# ZynqDDR.net
KiCad netlist of a schematic drawn in Altium Designer
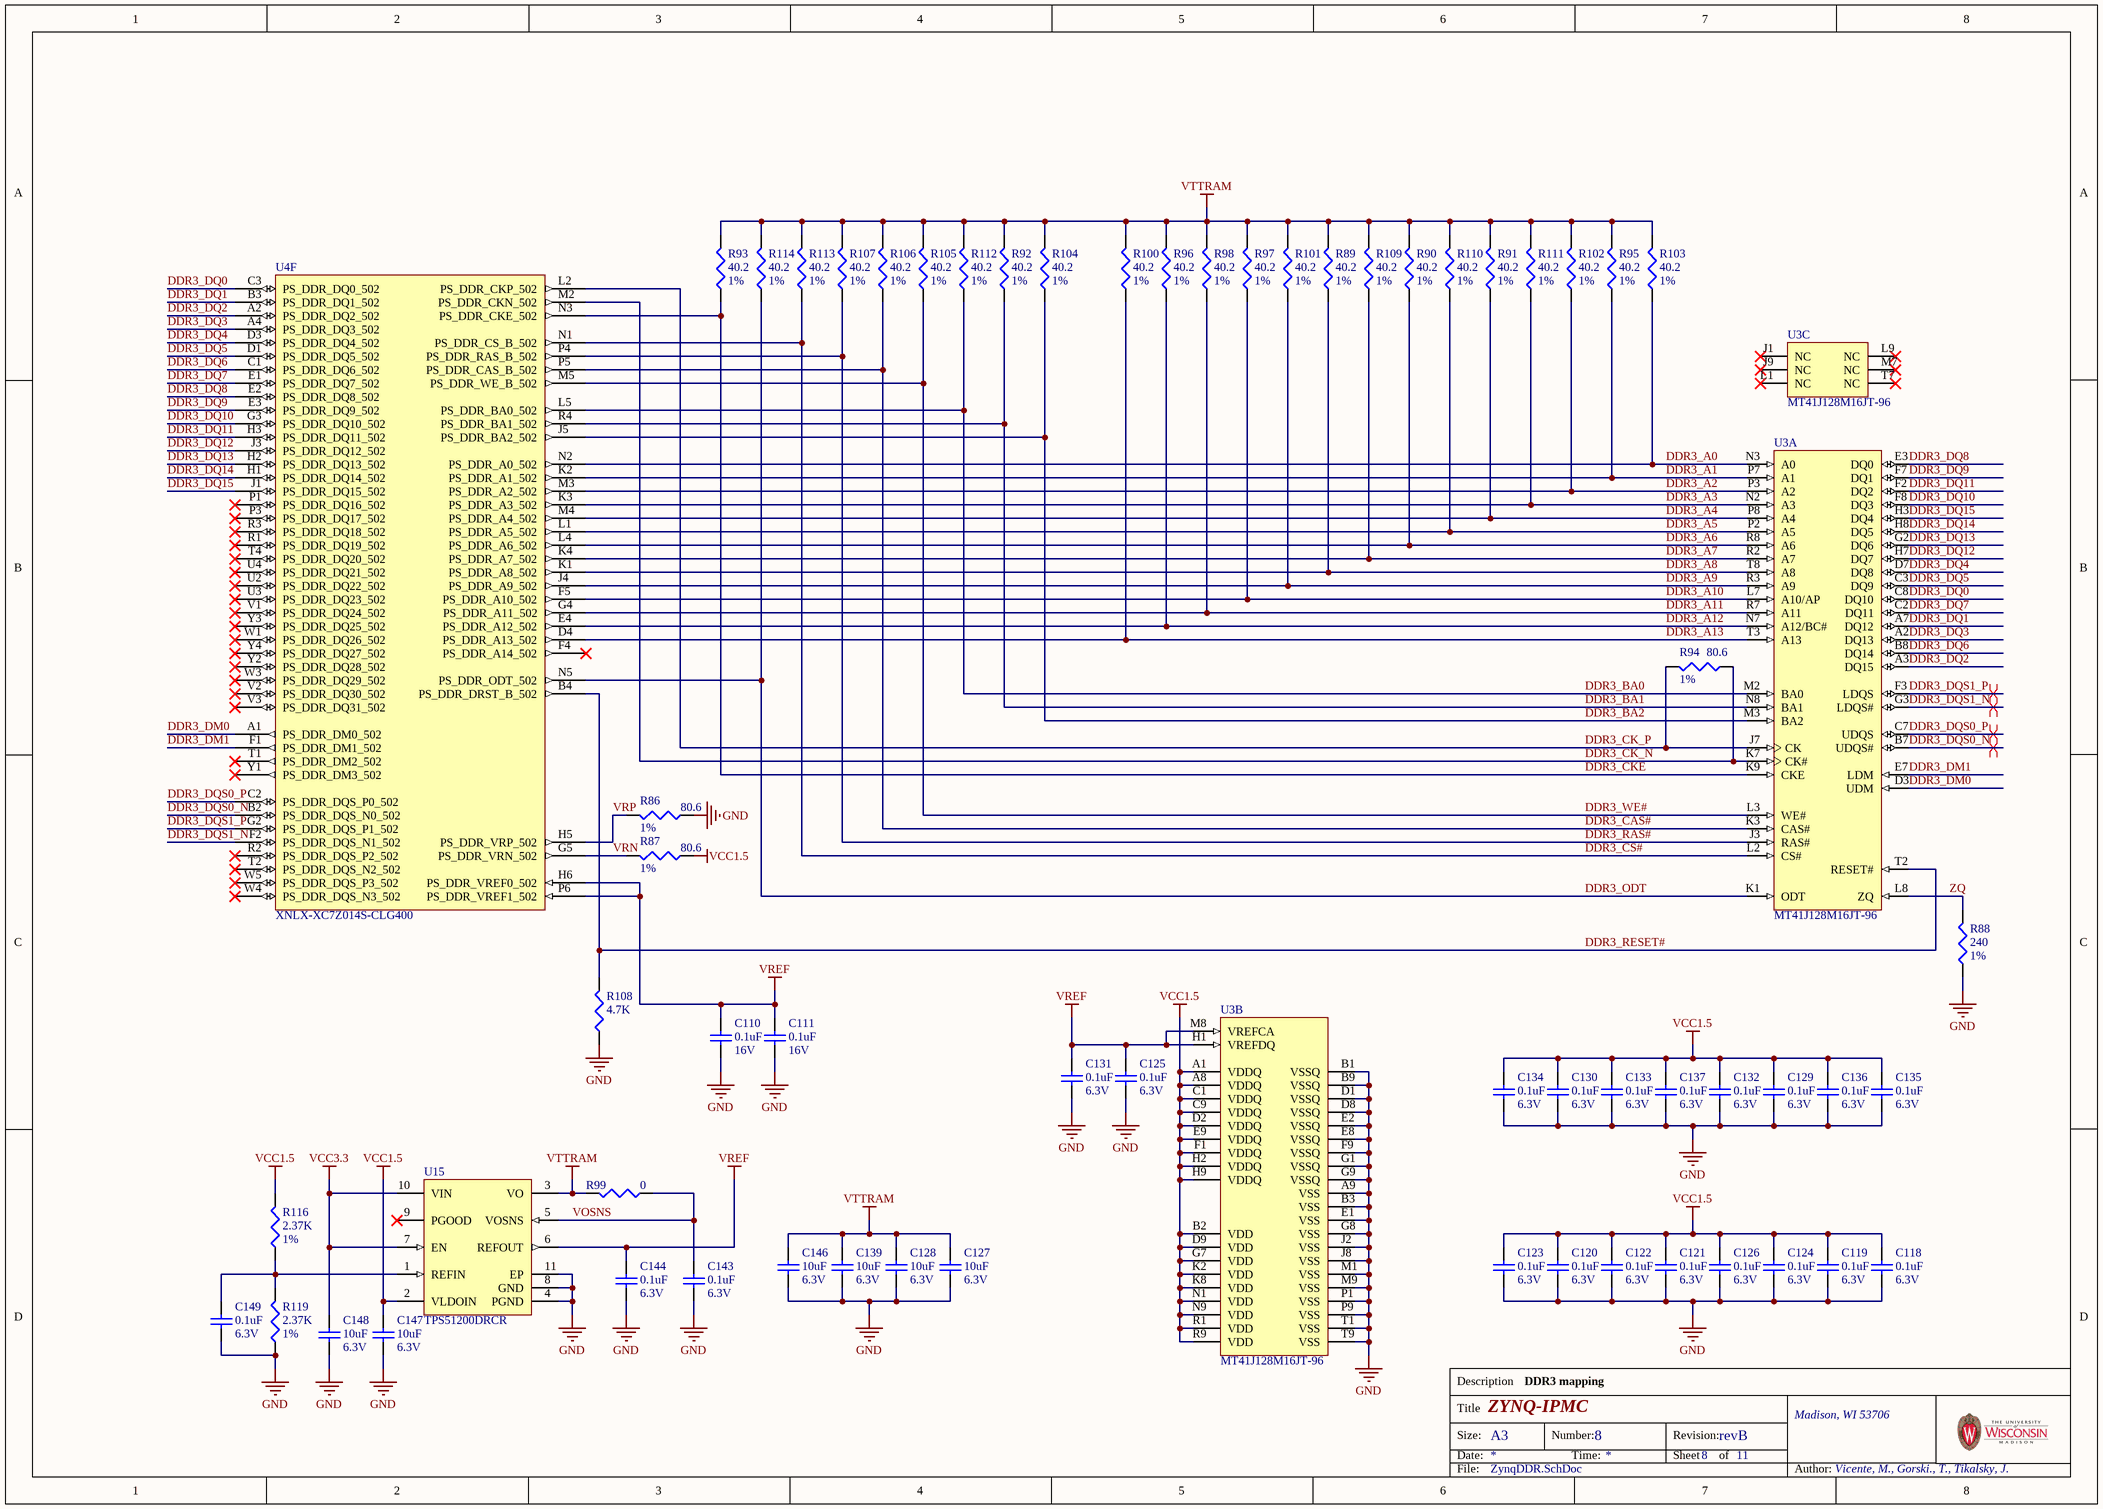
[diagram p0: ZynqDDR.SchDoc]

(export (version "E")
  (design (tool "Eeschema 10.0.6"))
  (components
    (comp (ref "C110")
      (value "0.1uF")
      (footprint "C0402_IPC_H")
      (description "Capacitor")
      (fields
        (field (name "RATING") "16V")
        (field (name "MANUFACTURER") "Murata")
        (field (name "PART") "GRM155R71C104KA88D")
      )
      (libsource (lib "CustomParts") (part "Cap"))
    )
    (comp (ref "C111")
      (value "0.1uF")
      (footprint "C0402_IPC_H")
      (description "Capacitor")
      (fields
        (field (name "RATING") "16V")
        (field (name "MANUFACTURER") "Murata")
        (field (name "PART") "GRM155R71C104KA88D")
      )
      (libsource (lib "CustomParts") (part "Cap"))
    )
    (comp (ref "C118")
      (value "0.1uF")
      (footprint "C0201_IPC_H")
      (description "Capacitor")
      (fields
        (field (name "RATING") "6.3V")
        (field (name "MANUFACTURER") "Murata")
        (field (name "PART") "GRM033R60J104KE19D")
      )
      (libsource (lib "CustomParts") (part "Cap"))
    )
    (comp (ref "C119")
      (value "0.1uF")
      (footprint "C0201_IPC_H")
      (description "Capacitor")
      (fields
        (field (name "RATING") "6.3V")
        (field (name "MANUFACTURER") "Murata")
        (field (name "PART") "GRM033R60J104KE19D")
      )
      (libsource (lib "CustomParts") (part "Cap"))
    )
    (comp (ref "C120")
      (value "0.1uF")
      (footprint "C0201_IPC_H")
      (description "Capacitor")
      (fields
        (field (name "RATING") "6.3V")
        (field (name "MANUFACTURER") "Murata")
        (field (name "PART") "GRM033R60J104KE19D")
      )
      (libsource (lib "CustomParts") (part "Cap"))
    )
    (comp (ref "C121")
      (value "0.1uF")
      (footprint "C0201_IPC_H")
      (description "Capacitor")
      (fields
        (field (name "RATING") "6.3V")
        (field (name "MANUFACTURER") "Murata")
        (field (name "PART") "GRM033R60J104KE19D")
      )
      (libsource (lib "CustomParts") (part "Cap"))
    )
    (comp (ref "C122")
      (value "0.1uF")
      (footprint "C0201_IPC_H")
      (description "Capacitor")
      (fields
        (field (name "RATING") "6.3V")
        (field (name "MANUFACTURER") "Murata")
        (field (name "PART") "GRM033R60J104KE19D")
      )
      (libsource (lib "CustomParts") (part "Cap"))
    )
    (comp (ref "C123")
      (value "0.1uF")
      (footprint "C0201_IPC_H")
      (description "Capacitor")
      (fields
        (field (name "RATING") "6.3V")
        (field (name "MANUFACTURER") "Murata")
        (field (name "PART") "GRM033R60J104KE19D")
      )
      (libsource (lib "CustomParts") (part "Cap"))
    )
    (comp (ref "C124")
      (value "0.1uF")
      (footprint "C0201_IPC_H")
      (description "Capacitor")
      (fields
        (field (name "RATING") "6.3V")
        (field (name "MANUFACTURER") "Murata")
        (field (name "PART") "GRM033R60J104KE19D")
      )
      (libsource (lib "CustomParts") (part "Cap"))
    )
    (comp (ref "C125")
      (value "0.1uF")
      (footprint "C0201_IPC_H")
      (description "Capacitor")
      (fields
        (field (name "RATING") "6.3V")
        (field (name "MANUFACTURER") "Murata")
        (field (name "PART") "GRM033R60J104KE19D")
      )
      (libsource (lib "CustomParts") (part "Cap"))
    )
    (comp (ref "C126")
      (value "0.1uF")
      (footprint "C0201_IPC_H")
      (description "Capacitor")
      (fields
        (field (name "RATING") "6.3V")
        (field (name "MANUFACTURER") "Murata")
        (field (name "PART") "GRM033R60J104KE19D")
      )
      (libsource (lib "CustomParts") (part "Cap"))
    )
    (comp (ref "C127")
      (value "10uF")
      (footprint "C0402_IPC_H")
      (description "Capacitor")
      (fields
        (field (name "RATING") "6.3V")
        (field (name "MANUFACTURER") "Murata")
        (field (name "PART") "GRM155R60J106ME44D")
      )
      (libsource (lib "CustomParts") (part "Cap"))
    )
    (comp (ref "C128")
      (value "10uF")
      (footprint "C0402_IPC_H")
      (description "Capacitor")
      (fields
        (field (name "RATING") "6.3V")
        (field (name "MANUFACTURER") "Murata")
        (field (name "PART") "GRM155R60J106ME44D")
      )
      (libsource (lib "CustomParts") (part "Cap"))
    )
    (comp (ref "C129")
      (value "0.1uF")
      (footprint "C0201_IPC_H")
      (description "Capacitor")
      (fields
        (field (name "RATING") "6.3V")
        (field (name "MANUFACTURER") "Murata")
        (field (name "PART") "GRM033R60J104KE19D")
      )
      (libsource (lib "CustomParts") (part "Cap"))
    )
    (comp (ref "C130")
      (value "0.1uF")
      (footprint "C0201_IPC_H")
      (description "Capacitor")
      (fields
        (field (name "RATING") "6.3V")
        (field (name "MANUFACTURER") "Murata")
        (field (name "PART") "GRM033R60J104KE19D")
      )
      (libsource (lib "CustomParts") (part "Cap"))
    )
    (comp (ref "C131")
      (value "0.1uF")
      (footprint "C0201_IPC_H")
      (description "Capacitor")
      (fields
        (field (name "RATING") "6.3V")
        (field (name "MANUFACTURER") "Murata")
        (field (name "PART") "GRM033R60J104KE19D")
      )
      (libsource (lib "CustomParts") (part "Cap"))
    )
    (comp (ref "C132")
      (value "0.1uF")
      (footprint "C0201_IPC_H")
      (description "Capacitor")
      (fields
        (field (name "RATING") "6.3V")
        (field (name "MANUFACTURER") "Murata")
        (field (name "PART") "GRM033R60J104KE19D")
      )
      (libsource (lib "CustomParts") (part "Cap"))
    )
    (comp (ref "C133")
      (value "0.1uF")
      (footprint "C0201_IPC_H")
      (description "Capacitor")
      (fields
        (field (name "RATING") "6.3V")
        (field (name "MANUFACTURER") "Murata")
        (field (name "PART") "GRM033R60J104KE19D")
      )
      (libsource (lib "CustomParts") (part "Cap"))
    )
    (comp (ref "C134")
      (value "0.1uF")
      (footprint "C0201_IPC_H")
      (description "Capacitor")
      (fields
        (field (name "RATING") "6.3V")
        (field (name "MANUFACTURER") "Murata")
        (field (name "PART") "GRM033R60J104KE19D")
      )
      (libsource (lib "CustomParts") (part "Cap"))
    )
    (comp (ref "C135")
      (value "0.1uF")
      (footprint "C0201_IPC_H")
      (description "Capacitor")
      (fields
        (field (name "RATING") "6.3V")
        (field (name "MANUFACTURER") "Murata")
        (field (name "PART") "GRM033R60J104KE19D")
      )
      (libsource (lib "CustomParts") (part "Cap"))
    )
    (comp (ref "C136")
      (value "0.1uF")
      (footprint "C0201_IPC_H")
      (description "Capacitor")
      (fields
        (field (name "RATING") "6.3V")
        (field (name "MANUFACTURER") "Murata")
        (field (name "PART") "GRM033R60J104KE19D")
      )
      (libsource (lib "CustomParts") (part "Cap"))
    )
    (comp (ref "C137")
      (value "0.1uF")
      (footprint "C0201_IPC_H")
      (description "Capacitor")
      (fields
        (field (name "RATING") "6.3V")
        (field (name "MANUFACTURER") "Murata")
        (field (name "PART") "GRM033R60J104KE19D")
      )
      (libsource (lib "CustomParts") (part "Cap"))
    )
    (comp (ref "C139")
      (value "10uF")
      (footprint "C0402_IPC_H")
      (description "Capacitor")
      (fields
        (field (name "RATING") "6.3V")
        (field (name "MANUFACTURER") "Murata")
        (field (name "PART") "GRM155R60J106ME44D")
      )
      (libsource (lib "CustomParts") (part "Cap"))
    )
    (comp (ref "C143")
      (value "0.1uF")
      (footprint "C0201_IPC_H")
      (description "Capacitor")
      (fields
        (field (name "RATING") "6.3V")
        (field (name "MANUFACTURER") "Murata")
        (field (name "PART") "GRM033R60J104KE19D")
      )
      (libsource (lib "CustomParts") (part "Cap"))
    )
    (comp (ref "C144")
      (value "0.1uF")
      (footprint "C0201_IPC_H")
      (description "Capacitor")
      (fields
        (field (name "RATING") "6.3V")
        (field (name "MANUFACTURER") "Murata")
        (field (name "PART") "GRM033R60J104KE19D")
      )
      (libsource (lib "CustomParts") (part "Cap"))
    )
    (comp (ref "C146")
      (value "10uF")
      (footprint "C0402_IPC_H")
      (description "Capacitor")
      (fields
        (field (name "RATING") "6.3V")
        (field (name "MANUFACTURER") "Murata")
        (field (name "PART") "GRM155R60J106ME44D")
      )
      (libsource (lib "CustomParts") (part "Cap"))
    )
    (comp (ref "C147")
      (value "10uF")
      (footprint "C0402_IPC_H")
      (description "Capacitor")
      (fields
        (field (name "RATING") "6.3V")
        (field (name "MANUFACTURER") "Murata")
        (field (name "PART") "GRM155R60J106ME44D")
      )
      (libsource (lib "CustomParts") (part "Cap"))
    )
    (comp (ref "C148")
      (value "10uF")
      (footprint "C0402_IPC_H")
      (description "Capacitor")
      (fields
        (field (name "RATING") "6.3V")
        (field (name "MANUFACTURER") "Murata")
        (field (name "PART") "GRM155R60J106ME44D")
      )
      (libsource (lib "CustomParts") (part "Cap"))
    )
    (comp (ref "C149")
      (value "0.1uF")
      (footprint "C0201_IPC_H")
      (description "Capacitor")
      (fields
        (field (name "RATING") "6.3V")
        (field (name "MANUFACTURER") "Murata")
        (field (name "PART") "GRM033R60J104KE19D")
      )
      (libsource (lib "CustomParts") (part "Cap"))
    )
    (comp (ref "R86")
      (value "80.6")
      (footprint "R0402_IPC_H")
      (description "Resistor")
      (fields
        (field (name "TOLERANCE") "1%")
        (field (name "MANUFACTURER") "Panasonic-ECG")
        (field (name "PART") "ERJ-2RKF80R6X")
      )
      (libsource (lib "CustomParts") (part "Res"))
    )
    (comp (ref "R87")
      (value "80.6")
      (footprint "R0402_IPC_H")
      (description "Resistor")
      (fields
        (field (name "TOLERANCE") "1%")
        (field (name "MANUFACTURER") "Panasonic-ECG")
        (field (name "PART") "ERJ-2RKF80R6X")
      )
      (libsource (lib "CustomParts") (part "Res"))
    )
    (comp (ref "R88")
      (value "240")
      (footprint "R0402_IPC_H")
      (description "Resistor")
      (fields
        (field (name "TOLERANCE") "1%")
        (field (name "MANUFACTURER") "Panasonic-ECG")
        (field (name "PART") "ERJ-2RKF2400X")
      )
      (libsource (lib "CustomParts") (part "Res"))
    )
    (comp (ref "R89")
      (value "40.2")
      (footprint "R0201_IPC_H")
      (description "Resistor")
      (fields
        (field (name "TOLERANCE") "1%")
        (field (name "MANUFACTURER") "Panasonic-ECG")
        (field (name "PART") "ERJ-1GEF40R2C")
      )
      (libsource (lib "CustomParts") (part "Res"))
    )
    (comp (ref "R90")
      (value "40.2")
      (footprint "R0201_IPC_H")
      (description "Resistor")
      (fields
        (field (name "TOLERANCE") "1%")
        (field (name "MANUFACTURER") "Panasonic-ECG")
        (field (name "PART") "ERJ-1GEF40R2C")
      )
      (libsource (lib "CustomParts") (part "Res"))
    )
    (comp (ref "R91")
      (value "40.2")
      (footprint "R0201_IPC_H")
      (description "Resistor")
      (fields
        (field (name "TOLERANCE") "1%")
        (field (name "MANUFACTURER") "Panasonic-ECG")
        (field (name "PART") "ERJ-1GEF40R2C")
      )
      (libsource (lib "CustomParts") (part "Res"))
    )
    (comp (ref "R92")
      (value "40.2")
      (footprint "R0201_IPC_H")
      (description "Resistor")
      (fields
        (field (name "TOLERANCE") "1%")
        (field (name "MANUFACTURER") "Panasonic-ECG")
        (field (name "PART") "ERJ-1GEF40R2C")
      )
      (libsource (lib "CustomParts") (part "Res"))
    )
    (comp (ref "R93")
      (value "40.2")
      (footprint "R0201_IPC_H")
      (description "Resistor")
      (fields
        (field (name "TOLERANCE") "1%")
        (field (name "MANUFACTURER") "Panasonic-ECG")
        (field (name "PART") "ERJ-1GEF40R2C")
      )
      (libsource (lib "CustomParts") (part "Res"))
    )
    (comp (ref "R94")
      (value "80.6")
      (footprint "R0402_IPC_H")
      (description "Resistor")
      (fields
        (field (name "TOLERANCE") "1%")
        (field (name "MANUFACTURER") "Panasonic-ECG")
        (field (name "PART") "ERJ-2RKF80R6X")
      )
      (libsource (lib "CustomParts") (part "Res"))
    )
    (comp (ref "R95")
      (value "40.2")
      (footprint "R0201_IPC_H")
      (description "Resistor")
      (fields
        (field (name "TOLERANCE") "1%")
        (field (name "MANUFACTURER") "Panasonic-ECG")
        (field (name "PART") "ERJ-1GEF40R2C")
      )
      (libsource (lib "CustomParts") (part "Res"))
    )
    (comp (ref "R96")
      (value "40.2")
      (footprint "R0201_IPC_H")
      (description "Resistor")
      (fields
        (field (name "TOLERANCE") "1%")
        (field (name "MANUFACTURER") "Panasonic-ECG")
        (field (name "PART") "ERJ-1GEF40R2C")
      )
      (libsource (lib "CustomParts") (part "Res"))
    )
    (comp (ref "R97")
      (value "40.2")
      (footprint "R0201_IPC_H")
      (description "Resistor")
      (fields
        (field (name "TOLERANCE") "1%")
        (field (name "MANUFACTURER") "Panasonic-ECG")
        (field (name "PART") "ERJ-1GEF40R2C")
      )
      (libsource (lib "CustomParts") (part "Res"))
    )
    (comp (ref "R98")
      (value "40.2")
      (footprint "R0201_IPC_H")
      (description "Resistor")
      (fields
        (field (name "TOLERANCE") "1%")
        (field (name "MANUFACTURER") "Panasonic-ECG")
        (field (name "PART") "ERJ-1GEF40R2C")
      )
      (libsource (lib "CustomParts") (part "Res"))
    )
    (comp (ref "R99")
      (value "0")
      (footprint "R0402_IPC_H")
      (description "Resistor")
      (fields (field (name "TOLERANCE") "5%") (field (name "MANUFACTURER") "Panasonic-ECG"))
      (libsource (lib "CustomParts") (part "Res"))
    )
    (comp (ref "R100")
      (value "40.2")
      (footprint "R0201_IPC_H")
      (description "Resistor")
      (fields
        (field (name "TOLERANCE") "1%")
        (field (name "MANUFACTURER") "Panasonic-ECG")
        (field (name "PART") "ERJ-1GEF40R2C")
      )
      (libsource (lib "CustomParts") (part "Res"))
    )
    (comp (ref "R101")
      (value "40.2")
      (footprint "R0201_IPC_H")
      (description "Resistor")
      (fields
        (field (name "TOLERANCE") "1%")
        (field (name "MANUFACTURER") "Panasonic-ECG")
        (field (name "PART") "ERJ-1GEF40R2C")
      )
      (libsource (lib "CustomParts") (part "Res"))
    )
    (comp (ref "R102")
      (value "40.2")
      (footprint "R0201_IPC_H")
      (description "Resistor")
      (fields
        (field (name "TOLERANCE") "1%")
        (field (name "MANUFACTURER") "Panasonic-ECG")
        (field (name "PART") "ERJ-1GEF40R2C")
      )
      (libsource (lib "CustomParts") (part "Res"))
    )
    (comp (ref "R103")
      (value "40.2")
      (footprint "R0201_IPC_H")
      (description "Resistor")
      (fields
        (field (name "TOLERANCE") "1%")
        (field (name "MANUFACTURER") "Panasonic-ECG")
        (field (name "PART") "ERJ-1GEF40R2C")
      )
      (libsource (lib "CustomParts") (part "Res"))
    )
    (comp (ref "R104")
      (value "40.2")
      (footprint "R0201_IPC_H")
      (description "Resistor")
      (fields
        (field (name "TOLERANCE") "1%")
        (field (name "MANUFACTURER") "Panasonic-ECG")
        (field (name "PART") "ERJ-1GEF40R2C")
      )
      (libsource (lib "CustomParts") (part "Res"))
    )
    (comp (ref "R105")
      (value "40.2")
      (footprint "R0201_IPC_H")
      (description "Resistor")
      (fields
        (field (name "TOLERANCE") "1%")
        (field (name "MANUFACTURER") "Panasonic-ECG")
        (field (name "PART") "ERJ-1GEF40R2C")
      )
      (libsource (lib "CustomParts") (part "Res"))
    )
    (comp (ref "R106")
      (value "40.2")
      (footprint "R0201_IPC_H")
      (description "Resistor")
      (fields
        (field (name "TOLERANCE") "1%")
        (field (name "MANUFACTURER") "Panasonic-ECG")
        (field (name "PART") "ERJ-1GEF40R2C")
      )
      (libsource (lib "CustomParts") (part "Res"))
    )
    (comp (ref "R107")
      (value "40.2")
      (footprint "R0201_IPC_H")
      (description "Resistor")
      (fields
        (field (name "TOLERANCE") "1%")
        (field (name "MANUFACTURER") "Panasonic-ECG")
        (field (name "PART") "ERJ-1GEF40R2C")
      )
      (libsource (lib "CustomParts") (part "Res"))
    )
    (comp (ref "R108")
      (value "4.7K")
      (footprint "R0402_IPC_H")
      (description "Resistor")
      (fields (field (name "TOLERANCE") "1%") (field (name "MANUFACTURER") "Panasonic"))
      (libsource (lib "CustomParts") (part "Res"))
    )
    (comp (ref "R109")
      (value "40.2")
      (footprint "R0201_IPC_H")
      (description "Resistor")
      (fields
        (field (name "TOLERANCE") "1%")
        (field (name "MANUFACTURER") "Panasonic-ECG")
        (field (name "PART") "ERJ-1GEF40R2C")
      )
      (libsource (lib "CustomParts") (part "Res"))
    )
    (comp (ref "R110")
      (value "40.2")
      (footprint "R0201_IPC_H")
      (description "Resistor")
      (fields
        (field (name "TOLERANCE") "1%")
        (field (name "MANUFACTURER") "Panasonic-ECG")
        (field (name "PART") "ERJ-1GEF40R2C")
      )
      (libsource (lib "CustomParts") (part "Res"))
    )
    (comp (ref "R111")
      (value "40.2")
      (footprint "R0201_IPC_H")
      (description "Resistor")
      (fields
        (field (name "TOLERANCE") "1%")
        (field (name "MANUFACTURER") "Panasonic-ECG")
        (field (name "PART") "ERJ-1GEF40R2C")
      )
      (libsource (lib "CustomParts") (part "Res"))
    )
    (comp (ref "R112")
      (value "40.2")
      (footprint "R0201_IPC_H")
      (description "Resistor")
      (fields
        (field (name "TOLERANCE") "1%")
        (field (name "MANUFACTURER") "Panasonic-ECG")
        (field (name "PART") "ERJ-1GEF40R2C")
      )
      (libsource (lib "CustomParts") (part "Res"))
    )
    (comp (ref "R113")
      (value "40.2")
      (footprint "R0201_IPC_H")
      (description "Resistor")
      (fields
        (field (name "TOLERANCE") "1%")
        (field (name "MANUFACTURER") "Panasonic-ECG")
        (field (name "PART") "ERJ-1GEF40R2C")
      )
      (libsource (lib "CustomParts") (part "Res"))
    )
    (comp (ref "R114")
      (value "40.2")
      (footprint "R0201_IPC_H")
      (description "Resistor")
      (fields
        (field (name "TOLERANCE") "1%")
        (field (name "MANUFACTURER") "Panasonic-ECG")
        (field (name "PART") "ERJ-1GEF40R2C")
      )
      (libsource (lib "CustomParts") (part "Res"))
    )
    (comp (ref "R116")
      (value "2.37K")
      (footprint "R0402_IPC_H")
      (description "Resistor")
      (fields
        (field (name "TOLERANCE") "1%")
        (field (name "MANUFACTURER") "Panasonic")
        (field (name "PART") "ERJ-2RKF2371X")
      )
      (libsource (lib "CustomParts") (part "Res"))
    )
    (comp (ref "R119")
      (value "2.37K")
      (footprint "R0402_IPC_H")
      (description "Resistor")
      (fields
        (field (name "TOLERANCE") "1%")
        (field (name "MANUFACTURER") "Panasonic")
        (field (name "PART") "ERJ-2RKF2371X")
      )
      (libsource (lib "CustomParts") (part "Res"))
    )
    (comp (ref "U3")
      (value "MT41J128M16JT-96")
      (footprint "MICT-JT-96")
      (fields (field (name "MANUFACTURER") "Micron") (field (name "PART") "MT41J128M16JT-125"))
      (libsource (lib "CustomParts") (part "MT41J128M16JT-96"))
    )
    (comp (ref "U4")
      (value "XNLX-XC7Z014S-CLG400")
      (footprint "CLG400")
      (fields (field (name "MANUFACTURER") "Xilinx") (field (name "PART") "XC7Z014S-1CLG400C"))
      (libsource (lib "CustomParts") (part "XNLX-XC7Z020-CLG400"))
    )
    (comp (ref "U15")
      (value "TPS51200DRCR")
      (footprint "DRC0010J_V")
      (fields (field (name "MANUFACTURER") "Texas Instruments"))
      (libsource (lib "altium-import") (part "root_0_TI-TPS51200DRC10-2400X1650TP_"))
    )
  )
  (nets
    (net (code "1") (name "/DDR3_A0") (class "Default")
      (node (ref "R103") (pin "1") (pinfunction "1_1") (pintype "passive"))
      (node (ref "U3") (pin "N3") (pinfunction "A0_N3") (pintype "input"))
      (node (ref "U4") (pin "N2") (pinfunction "PS_DDR_A0_502_N2") (pintype "output"))
    )
    (net (code "2") (name "/DDR3_A1") (class "Default")
      (node (ref "R95") (pin "1") (pinfunction "1_1") (pintype "passive"))
      (node (ref "U3") (pin "P7") (pinfunction "A1_P7") (pintype "input"))
      (node (ref "U4") (pin "K2") (pinfunction "PS_DDR_A1_502_K2") (pintype "output"))
    )
    (net (code "3") (name "/DDR3_A2") (class "Default")
      (node (ref "R102") (pin "1") (pinfunction "1_1") (pintype "passive"))
      (node (ref "U3") (pin "P3") (pinfunction "A2_P3") (pintype "input"))
      (node (ref "U4") (pin "M3") (pinfunction "PS_DDR_A2_502_M3") (pintype "output"))
    )
    (net (code "4") (name "/DDR3_A3") (class "Default")
      (node (ref "R111") (pin "1") (pinfunction "1_1") (pintype "passive"))
      (node (ref "U3") (pin "N2") (pinfunction "A3_N2") (pintype "input"))
      (node (ref "U4") (pin "K3") (pinfunction "PS_DDR_A3_502_K3") (pintype "output"))
    )
    (net (code "5") (name "/DDR3_A4") (class "Default")
      (node (ref "R91") (pin "1") (pinfunction "1_1") (pintype "passive"))
      (node (ref "U3") (pin "P8") (pinfunction "A4_P8") (pintype "input"))
      (node (ref "U4") (pin "M4") (pinfunction "PS_DDR_A4_502_M4") (pintype "output"))
    )
    (net (code "6") (name "/DDR3_A5") (class "Default")
      (node (ref "R110") (pin "1") (pinfunction "1_1") (pintype "passive"))
      (node (ref "U3") (pin "P2") (pinfunction "A5_P2") (pintype "input"))
      (node (ref "U4") (pin "L1") (pinfunction "PS_DDR_A5_502_L1") (pintype "output"))
    )
    (net (code "7") (name "/DDR3_A6") (class "Default")
      (node (ref "R90") (pin "1") (pinfunction "1_1") (pintype "passive"))
      (node (ref "U3") (pin "R8") (pinfunction "A6_R8") (pintype "input"))
      (node (ref "U4") (pin "L4") (pinfunction "PS_DDR_A6_502_L4") (pintype "output"))
    )
    (net (code "8") (name "/DDR3_A7") (class "Default")
      (node (ref "R109") (pin "1") (pinfunction "1_1") (pintype "passive"))
      (node (ref "U3") (pin "R2") (pinfunction "A7_R2") (pintype "input"))
      (node (ref "U4") (pin "K4") (pinfunction "PS_DDR_A7_502_K4") (pintype "output"))
    )
    (net (code "9") (name "/DDR3_A8") (class "Default")
      (node (ref "R89") (pin "1") (pinfunction "1_1") (pintype "passive"))
      (node (ref "U3") (pin "T8") (pinfunction "A8_T8") (pintype "input"))
      (node (ref "U4") (pin "K1") (pinfunction "PS_DDR_A8_502_K1") (pintype "output"))
    )
    (net (code "10") (name "/DDR3_A9") (class "Default")
      (node (ref "R101") (pin "1") (pinfunction "1_1") (pintype "passive"))
      (node (ref "U3") (pin "R3") (pinfunction "A9_R3") (pintype "input"))
      (node (ref "U4") (pin "J4") (pinfunction "PS_DDR_A9_502_J4") (pintype "output"))
    )
    (net (code "11") (name "/DDR3_A10") (class "Default")
      (node (ref "R97") (pin "1") (pinfunction "1_1") (pintype "passive"))
      (node (ref "U3") (pin "L7") (pinfunction "A10/AP_L7") (pintype "input"))
      (node (ref "U4") (pin "F5") (pinfunction "PS_DDR_A10_502_F5") (pintype "output"))
    )
    (net (code "12") (name "/DDR3_A11") (class "Default")
      (node (ref "R98") (pin "1") (pinfunction "1_1") (pintype "passive"))
      (node (ref "U3") (pin "R7") (pinfunction "A11_R7") (pintype "input"))
      (node (ref "U4") (pin "G4") (pinfunction "PS_DDR_A11_502_G4") (pintype "output"))
    )
    (net (code "13") (name "/DDR3_A12") (class "Default")
      (node (ref "R96") (pin "1") (pinfunction "1_1") (pintype "passive"))
      (node (ref "U3") (pin "N7") (pinfunction "A12/BC#_N7") (pintype "input"))
      (node (ref "U4") (pin "E4") (pinfunction "PS_DDR_A12_502_E4") (pintype "output"))
    )
    (net (code "14") (name "/DDR3_A13") (class "Default")
      (node (ref "R100") (pin "1") (pinfunction "1_1") (pintype "passive"))
      (node (ref "U3") (pin "T3") (pinfunction "A13_T3") (pintype "input"))
      (node (ref "U4") (pin "D4") (pinfunction "PS_DDR_A13_502_D4") (pintype "output"))
    )
    (net (code "15") (name "/DDR3_BA0") (class "Default")
      (node (ref "R112") (pin "1") (pinfunction "1_1") (pintype "passive"))
      (node (ref "U3") (pin "M2") (pinfunction "BA0_M2") (pintype "input"))
      (node (ref "U4") (pin "L5") (pinfunction "PS_DDR_BA0_502_L5") (pintype "output"))
    )
    (net (code "16") (name "/DDR3_BA1") (class "Default")
      (node (ref "R92") (pin "1") (pinfunction "1_1") (pintype "passive"))
      (node (ref "U3") (pin "N8") (pinfunction "BA1_N8") (pintype "input"))
      (node (ref "U4") (pin "R4") (pinfunction "PS_DDR_BA1_502_R4") (pintype "output"))
    )
    (net (code "17") (name "/DDR3_BA2") (class "Default")
      (node (ref "R104") (pin "1") (pinfunction "1_1") (pintype "passive"))
      (node (ref "U3") (pin "M3") (pinfunction "BA2_M3") (pintype "input"))
      (node (ref "U4") (pin "J5") (pinfunction "PS_DDR_BA2_502_J5") (pintype "output"))
    )
    (net (code "18") (name "/DDR3_CAS#") (class "Default")
      (node (ref "R106") (pin "1") (pinfunction "1_1") (pintype "passive"))
      (node (ref "U3") (pin "K3") (pinfunction "CAS#_K3") (pintype "input"))
      (node (ref "U4") (pin "P5") (pinfunction "PS_DDR_CAS_B_502_P5") (pintype "output"))
    )
    (net (code "19") (name "/DDR3_CKE") (class "Default")
      (node (ref "R93") (pin "1") (pinfunction "1_1") (pintype "passive"))
      (node (ref "U3") (pin "K9") (pinfunction "CKE_K9") (pintype "input"))
      (node (ref "U4") (pin "N3") (pinfunction "PS_DDR_CKE_502_N3") (pintype "output"))
    )
    (net (code "20") (name "/DDR3_CK_N") (class "Default")
      (node (ref "R94") (pin "1") (pinfunction "1_1") (pintype "passive"))
      (node (ref "U3") (pin "K7") (pinfunction "CK#_K7") (pintype "input"))
      (node (ref "U4") (pin "M2") (pinfunction "PS_DDR_CKN_502_M2") (pintype "output"))
    )
    (net (code "21") (name "/DDR3_CK_P") (class "Default")
      (node (ref "R94") (pin "2") (pinfunction "2_2") (pintype "passive"))
      (node (ref "U3") (pin "J7") (pinfunction "CK_J7") (pintype "input"))
      (node (ref "U4") (pin "L2") (pinfunction "PS_DDR_CKP_502_L2") (pintype "output"))
    )
    (net (code "22") (name "/DDR3_CS#") (class "Default")
      (node (ref "R113") (pin "1") (pinfunction "1_1") (pintype "passive"))
      (node (ref "U3") (pin "L2") (pinfunction "CS#_L2") (pintype "input"))
      (node (ref "U4") (pin "N1") (pinfunction "PS_DDR_CS_B_502_N1") (pintype "output"))
    )
    (net (code "23") (name "/DDR3_DM0") (class "Default")
      (node (ref "U3") (pin "D3") (pinfunction "UDM_D3") (pintype "input"))
      (node (ref "U4") (pin "A1") (pinfunction "PS_DDR_DM0_502_A1") (pintype "output"))
    )
    (net (code "24") (name "/DDR3_DM1") (class "Default")
      (node (ref "U3") (pin "E7") (pinfunction "LDM_E7") (pintype "input"))
      (node (ref "U4") (pin "F1") (pinfunction "PS_DDR_DM1_502_F1") (pintype "output"))
    )
    (net (code "25") (name "/DDR3_DQ0") (class "Default")
      (node (ref "U3") (pin "C8") (pinfunction "DQ10_C8") (pintype "bidirectional"))
      (node (ref "U4") (pin "C3") (pinfunction "PS_DDR_DQ0_502_C3") (pintype "bidirectional"))
    )
    (net (code "26") (name "/DDR3_DQ1") (class "Default")
      (node (ref "U3") (pin "A7") (pinfunction "DQ12_A7") (pintype "bidirectional"))
      (node (ref "U4") (pin "B3") (pinfunction "PS_DDR_DQ1_502_B3") (pintype "bidirectional"))
    )
    (net (code "27") (name "/DDR3_DQ2") (class "Default")
      (node (ref "U3") (pin "A3") (pinfunction "DQ15_A3") (pintype "bidirectional"))
      (node (ref "U4") (pin "A2") (pinfunction "PS_DDR_DQ2_502_A2") (pintype "bidirectional"))
    )
    (net (code "28") (name "/DDR3_DQ3") (class "Default")
      (node (ref "U3") (pin "A2") (pinfunction "DQ13_A2") (pintype "bidirectional"))
      (node (ref "U4") (pin "A4") (pinfunction "PS_DDR_DQ3_502_A4") (pintype "bidirectional"))
    )
    (net (code "29") (name "/DDR3_DQ4") (class "Default")
      (node (ref "U3") (pin "D7") (pinfunction "DQ8_D7") (pintype "bidirectional"))
      (node (ref "U4") (pin "D3") (pinfunction "PS_DDR_DQ4_502_D3") (pintype "bidirectional"))
    )
    (net (code "30") (name "/DDR3_DQ5") (class "Default")
      (node (ref "U3") (pin "C3") (pinfunction "DQ9_C3") (pintype "bidirectional"))
      (node (ref "U4") (pin "D1") (pinfunction "PS_DDR_DQ5_502_D1") (pintype "bidirectional"))
    )
    (net (code "31") (name "/DDR3_DQ6") (class "Default")
      (node (ref "U3") (pin "B8") (pinfunction "DQ14_B8") (pintype "bidirectional"))
      (node (ref "U4") (pin "C1") (pinfunction "PS_DDR_DQ6_502_C1") (pintype "bidirectional"))
    )
    (net (code "32") (name "/DDR3_DQ7") (class "Default")
      (node (ref "U3") (pin "C2") (pinfunction "DQ11_C2") (pintype "bidirectional"))
      (node (ref "U4") (pin "E1") (pinfunction "PS_DDR_DQ7_502_E1") (pintype "bidirectional"))
    )
    (net (code "33") (name "/DDR3_DQ8") (class "Default")
      (node (ref "U3") (pin "E3") (pinfunction "DQ0_E3") (pintype "bidirectional"))
      (node (ref "U4") (pin "E2") (pinfunction "PS_DDR_DQ8_502_E2") (pintype "bidirectional"))
    )
    (net (code "34") (name "/DDR3_DQ9") (class "Default")
      (node (ref "U3") (pin "F7") (pinfunction "DQ1_F7") (pintype "bidirectional"))
      (node (ref "U4") (pin "E3") (pinfunction "PS_DDR_DQ9_502_E3") (pintype "bidirectional"))
    )
    (net (code "35") (name "/DDR3_DQ10") (class "Default")
      (node (ref "U3") (pin "F8") (pinfunction "DQ3_F8") (pintype "bidirectional"))
      (node (ref "U4") (pin "G3") (pinfunction "PS_DDR_DQ10_502_G3") (pintype "bidirectional"))
    )
    (net (code "36") (name "/DDR3_DQ11") (class "Default")
      (node (ref "U3") (pin "F2") (pinfunction "DQ2_F2") (pintype "bidirectional"))
      (node (ref "U4") (pin "H3") (pinfunction "PS_DDR_DQ11_502_H3") (pintype "bidirectional"))
    )
    (net (code "37") (name "/DDR3_DQ12") (class "Default")
      (node (ref "U3") (pin "H7") (pinfunction "DQ7_H7") (pintype "bidirectional"))
      (node (ref "U4") (pin "J3") (pinfunction "PS_DDR_DQ12_502_J3") (pintype "bidirectional"))
    )
    (net (code "38") (name "/DDR3_DQ13") (class "Default")
      (node (ref "U3") (pin "G2") (pinfunction "DQ6_G2") (pintype "bidirectional"))
      (node (ref "U4") (pin "H2") (pinfunction "PS_DDR_DQ13_502_H2") (pintype "bidirectional"))
    )
    (net (code "39") (name "/DDR3_DQ14") (class "Default")
      (node (ref "U3") (pin "H8") (pinfunction "DQ5_H8") (pintype "bidirectional"))
      (node (ref "U4") (pin "H1") (pinfunction "PS_DDR_DQ14_502_H1") (pintype "bidirectional"))
    )
    (net (code "40") (name "/DDR3_DQ15") (class "Default")
      (node (ref "U3") (pin "H3") (pinfunction "DQ4_H3") (pintype "bidirectional"))
      (node (ref "U4") (pin "J1") (pinfunction "PS_DDR_DQ15_502_J1") (pintype "bidirectional"))
    )
    (net (code "41") (name "/DDR3_DQS0_N") (class "Default")
      (node (ref "U3") (pin "B7") (pinfunction "UDQS#_B7") (pintype "bidirectional"))
      (node (ref "U4") (pin "B2") (pinfunction "PS_DDR_DQS_N0_502_B2") (pintype "bidirectional"))
    )
    (net (code "42") (name "/DDR3_DQS0_P") (class "Default")
      (node (ref "U3") (pin "C7") (pinfunction "UDQS_C7") (pintype "bidirectional"))
      (node (ref "U4") (pin "C2") (pinfunction "PS_DDR_DQS_P0_502_C2") (pintype "bidirectional"))
    )
    (net (code "43") (name "/DDR3_DQS1_N") (class "Default")
      (node (ref "U3") (pin "G3") (pinfunction "LDQS#_G3") (pintype "bidirectional"))
      (node (ref "U4") (pin "F2") (pinfunction "PS_DDR_DQS_N1_502_F2") (pintype "bidirectional"))
    )
    (net (code "44") (name "/DDR3_DQS1_P") (class "Default")
      (node (ref "U3") (pin "F3") (pinfunction "LDQS_F3") (pintype "bidirectional"))
      (node (ref "U4") (pin "G2") (pinfunction "PS_DDR_DQS_P1_502_G2") (pintype "bidirectional"))
    )
    (net (code "45") (name "/DDR3_ODT") (class "Default")
      (node (ref "R114") (pin "1") (pinfunction "1_1") (pintype "passive"))
      (node (ref "U3") (pin "K1") (pinfunction "ODT_K1") (pintype "input"))
      (node (ref "U4") (pin "N5") (pinfunction "PS_DDR_ODT_502_N5") (pintype "output"))
    )
    (net (code "46") (name "/DDR3_RAS#") (class "Default")
      (node (ref "R107") (pin "1") (pinfunction "1_1") (pintype "passive"))
      (node (ref "U3") (pin "J3") (pinfunction "RAS#_J3") (pintype "input"))
      (node (ref "U4") (pin "P4") (pinfunction "PS_DDR_RAS_B_502_P4") (pintype "output"))
    )
    (net (code "47") (name "/DDR3_RESET#") (class "Default")
      (node (ref "R108") (pin "2") (pinfunction "2_2") (pintype "passive"))
      (node (ref "U3") (pin "T2") (pinfunction "RESET#_T2") (pintype "input"))
      (node (ref "U4") (pin "B4") (pinfunction "PS_DDR_DRST_B_502_B4") (pintype "output"))
    )
    (net (code "48") (name "/DDR3_WE#") (class "Default")
      (node (ref "R105") (pin "1") (pinfunction "1_1") (pintype "passive"))
      (node (ref "U3") (pin "L3") (pinfunction "WE#_L3") (pintype "input"))
      (node (ref "U4") (pin "M5") (pinfunction "PS_DDR_WE_B_502_M5") (pintype "output"))
    )
    (net (code "49") (name "/VOSNS") (class "Default")
      (node (ref "C143") (pin "2") (pinfunction "2_2") (pintype "passive"))
      (node (ref "R99") (pin "1") (pinfunction "1_1") (pintype "passive"))
      (node (ref "U15") (pin "5") (pinfunction "VOSNS_5") (pintype "input"))
    )
    (net (code "50") (name "/VRN") (class "Default")
      (node (ref "R87") (pin "2") (pinfunction "2_2") (pintype "passive"))
      (node (ref "U4") (pin "G5") (pinfunction "PS_DDR_VRN_502_G5") (pintype "output"))
    )
    (net (code "51") (name "/VRP") (class "Default")
      (node (ref "R86") (pin "2") (pinfunction "2_2") (pintype "passive"))
      (node (ref "U4") (pin "H5") (pinfunction "PS_DDR_VRP_502_H5") (pintype "output"))
    )
    (net (code "52") (name "/ZQ") (class "Default")
      (node (ref "R88") (pin "2") (pinfunction "2_2") (pintype "passive"))
      (node (ref "U3") (pin "L8") (pinfunction "ZQ_L8") (pintype "input"))
    )
    (net (code "53") (name "GND") (class "Default")
      (node (ref "C110") (pin "1") (pinfunction "1_1") (pintype "passive"))
      (node (ref "C111") (pin "1") (pinfunction "1_1") (pintype "passive"))
      (node (ref "C118") (pin "2") (pinfunction "2_2") (pintype "passive"))
      (node (ref "C119") (pin "2") (pinfunction "2_2") (pintype "passive"))
      (node (ref "C120") (pin "2") (pinfunction "2_2") (pintype "passive"))
      (node (ref "C121") (pin "2") (pinfunction "2_2") (pintype "passive"))
      (node (ref "C122") (pin "2") (pinfunction "2_2") (pintype "passive"))
      (node (ref "C123") (pin "2") (pinfunction "2_2") (pintype "passive"))
      (node (ref "C124") (pin "2") (pinfunction "2_2") (pintype "passive"))
      (node (ref "C125") (pin "1") (pinfunction "1_1") (pintype "passive"))
      (node (ref "C126") (pin "2") (pinfunction "2_2") (pintype "passive"))
      (node (ref "C127") (pin "1") (pinfunction "1_1") (pintype "passive"))
      (node (ref "C128") (pin "1") (pinfunction "1_1") (pintype "passive"))
      (node (ref "C129") (pin "2") (pinfunction "2_2") (pintype "passive"))
      (node (ref "C130") (pin "2") (pinfunction "2_2") (pintype "passive"))
      (node (ref "C131") (pin "1") (pinfunction "1_1") (pintype "passive"))
      (node (ref "C132") (pin "2") (pinfunction "2_2") (pintype "passive"))
      (node (ref "C133") (pin "2") (pinfunction "2_2") (pintype "passive"))
      (node (ref "C134") (pin "2") (pinfunction "2_2") (pintype "passive"))
      (node (ref "C135") (pin "2") (pinfunction "2_2") (pintype "passive"))
      (node (ref "C136") (pin "2") (pinfunction "2_2") (pintype "passive"))
      (node (ref "C137") (pin "2") (pinfunction "2_2") (pintype "passive"))
      (node (ref "C139") (pin "1") (pinfunction "1_1") (pintype "passive"))
      (node (ref "C143") (pin "1") (pinfunction "1_1") (pintype "passive"))
      (node (ref "C144") (pin "1") (pinfunction "1_1") (pintype "passive"))
      (node (ref "C146") (pin "1") (pinfunction "1_1") (pintype "passive"))
      (node (ref "C147") (pin "1") (pinfunction "1_1") (pintype "passive"))
      (node (ref "C148") (pin "1") (pinfunction "1_1") (pintype "passive"))
      (node (ref "C149") (pin "1") (pinfunction "1_1") (pintype "passive"))
      (node (ref "R108") (pin "1") (pinfunction "1_1") (pintype "passive"))
      (node (ref "R119") (pin "1") (pinfunction "1_1") (pintype "passive"))
      (node (ref "R86") (pin "1") (pinfunction "1_1") (pintype "passive"))
      (node (ref "R88") (pin "1") (pinfunction "1_1") (pintype "passive"))
      (node (ref "U15") (pin "11") (pinfunction "EP_11") (pintype "power_in"))
      (node (ref "U15") (pin "4") (pinfunction "PGND_4") (pintype "power_in"))
      (node (ref "U15") (pin "8") (pinfunction "GND_8") (pintype "power_in"))
      (node (ref "U3") (pin "A9") (pinfunction "VSS_A9") (pintype "power_in"))
      (node (ref "U3") (pin "B1") (pinfunction "VSSQ_B1") (pintype "power_in"))
      (node (ref "U3") (pin "B3") (pinfunction "VSS_B3") (pintype "power_in"))
      (node (ref "U3") (pin "B9") (pinfunction "VSSQ_B9") (pintype "power_in"))
      (node (ref "U3") (pin "D1") (pinfunction "VSSQ_D1") (pintype "power_in"))
      (node (ref "U3") (pin "D8") (pinfunction "VSSQ_D8") (pintype "power_in"))
      (node (ref "U3") (pin "E1") (pinfunction "VSS_E1") (pintype "power_in"))
      (node (ref "U3") (pin "E2") (pinfunction "VSSQ_E2") (pintype "power_in"))
      (node (ref "U3") (pin "E8") (pinfunction "VSSQ_E8") (pintype "power_in"))
      (node (ref "U3") (pin "F9") (pinfunction "VSSQ_F9") (pintype "power_in"))
      (node (ref "U3") (pin "G1") (pinfunction "VSSQ_G1") (pintype "power_in"))
      (node (ref "U3") (pin "G8") (pinfunction "VSS_G8") (pintype "power_in"))
      (node (ref "U3") (pin "G9") (pinfunction "VSSQ_G9") (pintype "power_in"))
      (node (ref "U3") (pin "J2") (pinfunction "VSS_J2") (pintype "power_in"))
      (node (ref "U3") (pin "J8") (pinfunction "VSS_J8") (pintype "power_in"))
      (node (ref "U3") (pin "M1") (pinfunction "VSS_M1") (pintype "power_in"))
      (node (ref "U3") (pin "M9") (pinfunction "VSS_M9") (pintype "power_in"))
      (node (ref "U3") (pin "P1") (pinfunction "VSS_P1") (pintype "power_in"))
      (node (ref "U3") (pin "P9") (pinfunction "VSS_P9") (pintype "power_in"))
      (node (ref "U3") (pin "T1") (pinfunction "VSS_T1") (pintype "power_in"))
      (node (ref "U3") (pin "T9") (pinfunction "VSS_T9") (pintype "power_in"))
    )
    (net (code "54") (name "Net-(U15-REFIN)") (class "Default")
      (node (ref "C149") (pin "2") (pinfunction "2_2") (pintype "passive"))
      (node (ref "R116") (pin "1") (pinfunction "1_1") (pintype "passive"))
      (node (ref "R119") (pin "2") (pinfunction "2_2") (pintype "passive"))
      (node (ref "U15") (pin "1") (pinfunction "REFIN_1") (pintype "input"))
    )
    (net (code "55") (name "VCC1.5") (class "Default")
      (node (ref "C118") (pin "1") (pinfunction "1_1") (pintype "passive"))
      (node (ref "C119") (pin "1") (pinfunction "1_1") (pintype "passive"))
      (node (ref "C120") (pin "1") (pinfunction "1_1") (pintype "passive"))
      (node (ref "C121") (pin "1") (pinfunction "1_1") (pintype "passive"))
      (node (ref "C122") (pin "1") (pinfunction "1_1") (pintype "passive"))
      (node (ref "C123") (pin "1") (pinfunction "1_1") (pintype "passive"))
      (node (ref "C124") (pin "1") (pinfunction "1_1") (pintype "passive"))
      (node (ref "C126") (pin "1") (pinfunction "1_1") (pintype "passive"))
      (node (ref "C129") (pin "1") (pinfunction "1_1") (pintype "passive"))
      (node (ref "C130") (pin "1") (pinfunction "1_1") (pintype "passive"))
      (node (ref "C132") (pin "1") (pinfunction "1_1") (pintype "passive"))
      (node (ref "C133") (pin "1") (pinfunction "1_1") (pintype "passive"))
      (node (ref "C134") (pin "1") (pinfunction "1_1") (pintype "passive"))
      (node (ref "C135") (pin "1") (pinfunction "1_1") (pintype "passive"))
      (node (ref "C136") (pin "1") (pinfunction "1_1") (pintype "passive"))
      (node (ref "C137") (pin "1") (pinfunction "1_1") (pintype "passive"))
      (node (ref "C147") (pin "2") (pinfunction "2_2") (pintype "passive"))
      (node (ref "R116") (pin "2") (pinfunction "2_2") (pintype "passive"))
      (node (ref "R87") (pin "1") (pinfunction "1_1") (pintype "passive"))
      (node (ref "U15") (pin "2") (pinfunction "VLDOIN_2") (pintype "power_in"))
      (node (ref "U3") (pin "A1") (pinfunction "VDDQ_A1") (pintype "power_in"))
      (node (ref "U3") (pin "A8") (pinfunction "VDDQ_A8") (pintype "power_in"))
      (node (ref "U3") (pin "B2") (pinfunction "VDD_B2") (pintype "power_in"))
      (node (ref "U3") (pin "C1") (pinfunction "VDDQ_C1") (pintype "power_in"))
      (node (ref "U3") (pin "C9") (pinfunction "VDDQ_C9") (pintype "power_in"))
      (node (ref "U3") (pin "D2") (pinfunction "VDDQ_D2") (pintype "power_in"))
      (node (ref "U3") (pin "D9") (pinfunction "VDD_D9") (pintype "power_in"))
      (node (ref "U3") (pin "E9") (pinfunction "VDDQ_E9") (pintype "power_in"))
      (node (ref "U3") (pin "F1") (pinfunction "VDDQ_F1") (pintype "power_in"))
      (node (ref "U3") (pin "G7") (pinfunction "VDD_G7") (pintype "power_in"))
      (node (ref "U3") (pin "H2") (pinfunction "VDDQ_H2") (pintype "power_in"))
      (node (ref "U3") (pin "H9") (pinfunction "VDDQ_H9") (pintype "power_in"))
      (node (ref "U3") (pin "K2") (pinfunction "VDD_K2") (pintype "power_in"))
      (node (ref "U3") (pin "K8") (pinfunction "VDD_K8") (pintype "power_in"))
      (node (ref "U3") (pin "N1") (pinfunction "VDD_N1") (pintype "power_in"))
      (node (ref "U3") (pin "N9") (pinfunction "VDD_N9") (pintype "power_in"))
      (node (ref "U3") (pin "R1") (pinfunction "VDD_R1") (pintype "power_in"))
      (node (ref "U3") (pin "R9") (pinfunction "VDD_R9") (pintype "power_in"))
    )
    (net (code "56") (name "VCC3.3") (class "Default")
      (node (ref "C148") (pin "2") (pinfunction "2_2") (pintype "passive"))
      (node (ref "U15") (pin "10") (pinfunction "VIN_10") (pintype "power_in"))
      (node (ref "U15") (pin "7") (pinfunction "EN_7") (pintype "input"))
    )
    (net (code "57") (name "VREF") (class "Default")
      (node (ref "C110") (pin "2") (pinfunction "2_2") (pintype "passive"))
      (node (ref "C111") (pin "2") (pinfunction "2_2") (pintype "passive"))
      (node (ref "C125") (pin "2") (pinfunction "2_2") (pintype "passive"))
      (node (ref "C131") (pin "2") (pinfunction "2_2") (pintype "passive"))
      (node (ref "C144") (pin "2") (pinfunction "2_2") (pintype "passive"))
      (node (ref "U15") (pin "6") (pinfunction "REFOUT_6") (pintype "output"))
      (node (ref "U3") (pin "H1") (pinfunction "VREFDQ_H1") (pintype "input"))
      (node (ref "U3") (pin "M8") (pinfunction "VREFCA_M8") (pintype "input"))
      (node (ref "U4") (pin "H6") (pinfunction "PS_DDR_VREF0_502_H6") (pintype "input"))
      (node (ref "U4") (pin "P6") (pinfunction "PS_DDR_VREF1_502_P6") (pintype "input"))
    )
    (net (code "58") (name "VTTRAM") (class "Default")
      (node (ref "C127") (pin "2") (pinfunction "2_2") (pintype "passive"))
      (node (ref "C128") (pin "2") (pinfunction "2_2") (pintype "passive"))
      (node (ref "C139") (pin "2") (pinfunction "2_2") (pintype "passive"))
      (node (ref "C146") (pin "2") (pinfunction "2_2") (pintype "passive"))
      (node (ref "R100") (pin "2") (pinfunction "2_2") (pintype "passive"))
      (node (ref "R101") (pin "2") (pinfunction "2_2") (pintype "passive"))
      (node (ref "R102") (pin "2") (pinfunction "2_2") (pintype "passive"))
      (node (ref "R103") (pin "2") (pinfunction "2_2") (pintype "passive"))
      (node (ref "R104") (pin "2") (pinfunction "2_2") (pintype "passive"))
      (node (ref "R105") (pin "2") (pinfunction "2_2") (pintype "passive"))
      (node (ref "R106") (pin "2") (pinfunction "2_2") (pintype "passive"))
      (node (ref "R107") (pin "2") (pinfunction "2_2") (pintype "passive"))
      (node (ref "R109") (pin "2") (pinfunction "2_2") (pintype "passive"))
      (node (ref "R110") (pin "2") (pinfunction "2_2") (pintype "passive"))
      (node (ref "R111") (pin "2") (pinfunction "2_2") (pintype "passive"))
      (node (ref "R112") (pin "2") (pinfunction "2_2") (pintype "passive"))
      (node (ref "R113") (pin "2") (pinfunction "2_2") (pintype "passive"))
      (node (ref "R114") (pin "2") (pinfunction "2_2") (pintype "passive"))
      (node (ref "R89") (pin "2") (pinfunction "2_2") (pintype "passive"))
      (node (ref "R90") (pin "2") (pinfunction "2_2") (pintype "passive"))
      (node (ref "R91") (pin "2") (pinfunction "2_2") (pintype "passive"))
      (node (ref "R92") (pin "2") (pinfunction "2_2") (pintype "passive"))
      (node (ref "R93") (pin "2") (pinfunction "2_2") (pintype "passive"))
      (node (ref "R95") (pin "2") (pinfunction "2_2") (pintype "passive"))
      (node (ref "R96") (pin "2") (pinfunction "2_2") (pintype "passive"))
      (node (ref "R97") (pin "2") (pinfunction "2_2") (pintype "passive"))
      (node (ref "R98") (pin "2") (pinfunction "2_2") (pintype "passive"))
      (node (ref "R99") (pin "2") (pinfunction "2_2") (pintype "passive"))
      (node (ref "U15") (pin "3") (pinfunction "VO_3") (pintype "power_in"))
    )
    (net (code "59") (name "unconnected-(U3C-NC-PadJ1)") (class "Default")
      (node (ref "U3") (pin "J1") (pinfunction "NC_J1") (pintype "passive+no_connect"))
    )
    (net (code "60") (name "unconnected-(U3C-NC-PadJ9)") (class "Default")
      (node (ref "U3") (pin "J9") (pinfunction "NC_J9") (pintype "passive+no_connect"))
    )
    (net (code "61") (name "unconnected-(U3C-NC-PadL1)") (class "Default")
      (node (ref "U3") (pin "L1") (pinfunction "NC_L1") (pintype "passive+no_connect"))
    )
    (net (code "62") (name "unconnected-(U3C-NC-PadL9)") (class "Default")
      (node (ref "U3") (pin "L9") (pinfunction "NC_L9") (pintype "passive+no_connect"))
    )
    (net (code "63") (name "unconnected-(U3C-NC-PadM7)") (class "Default")
      (node (ref "U3") (pin "M7") (pinfunction "NC_M7") (pintype "passive+no_connect"))
    )
    (net (code "64") (name "unconnected-(U3C-NC-PadT7)") (class "Default")
      (node (ref "U3") (pin "T7") (pinfunction "NC_T7") (pintype "passive+no_connect"))
    )
    (net (code "65") (name "unconnected-(U4F-PS_DDR_A14_502-PadF4)") (class "Default")
      (node (ref "U4") (pin "F4") (pinfunction "PS_DDR_A14_502_F4") (pintype "output+no_connect"))
    )
    (net (code "66") (name "unconnected-(U4F-PS_DDR_DM2_502-PadT1)") (class "Default")
      (node (ref "U4") (pin "T1") (pinfunction "PS_DDR_DM2_502_T1") (pintype "output+no_connect"))
    )
    (net (code "67") (name "unconnected-(U4F-PS_DDR_DM3_502-PadY1)") (class "Default")
      (node (ref "U4") (pin "Y1") (pinfunction "PS_DDR_DM3_502_Y1") (pintype "output+no_connect"))
    )
    (net (code "68") (name "unconnected-(U4F-PS_DDR_DQ16_502-PadP1)") (class "Default")
      (node (ref "U4") (pin "P1") (pinfunction "PS_DDR_DQ16_502_P1") (pintype "bidirectional+no_connect"))
    )
    (net (code "69") (name "unconnected-(U4F-PS_DDR_DQ17_502-PadP3)") (class "Default")
      (node (ref "U4") (pin "P3") (pinfunction "PS_DDR_DQ17_502_P3") (pintype "bidirectional+no_connect"))
    )
    (net (code "70") (name "unconnected-(U4F-PS_DDR_DQ18_502-PadR3)") (class "Default")
      (node (ref "U4") (pin "R3") (pinfunction "PS_DDR_DQ18_502_R3") (pintype "bidirectional+no_connect"))
    )
    (net (code "71") (name "unconnected-(U4F-PS_DDR_DQ19_502-PadR1)") (class "Default")
      (node (ref "U4") (pin "R1") (pinfunction "PS_DDR_DQ19_502_R1") (pintype "bidirectional+no_connect"))
    )
    (net (code "72") (name "unconnected-(U4F-PS_DDR_DQ20_502-PadT4)") (class "Default")
      (node (ref "U4") (pin "T4") (pinfunction "PS_DDR_DQ20_502_T4") (pintype "bidirectional+no_connect"))
    )
    (net (code "73") (name "unconnected-(U4F-PS_DDR_DQ21_502-PadU4)") (class "Default")
      (node (ref "U4") (pin "U4") (pinfunction "PS_DDR_DQ21_502_U4") (pintype "bidirectional+no_connect"))
    )
    (net (code "74") (name "unconnected-(U4F-PS_DDR_DQ22_502-PadU2)") (class "Default")
      (node (ref "U4") (pin "U2") (pinfunction "PS_DDR_DQ22_502_U2") (pintype "bidirectional+no_connect"))
    )
    (net (code "75") (name "unconnected-(U4F-PS_DDR_DQ23_502-PadU3)") (class "Default")
      (node (ref "U4") (pin "U3") (pinfunction "PS_DDR_DQ23_502_U3") (pintype "bidirectional+no_connect"))
    )
    (net (code "76") (name "unconnected-(U4F-PS_DDR_DQ24_502-PadV1)") (class "Default")
      (node (ref "U4") (pin "V1") (pinfunction "PS_DDR_DQ24_502_V1") (pintype "bidirectional+no_connect"))
    )
    (net (code "77") (name "unconnected-(U4F-PS_DDR_DQ25_502-PadY3)") (class "Default")
      (node (ref "U4") (pin "Y3") (pinfunction "PS_DDR_DQ25_502_Y3") (pintype "bidirectional+no_connect"))
    )
    (net (code "78") (name "unconnected-(U4F-PS_DDR_DQ26_502-PadW1)") (class "Default")
      (node (ref "U4") (pin "W1") (pinfunction "PS_DDR_DQ26_502_W1") (pintype "bidirectional+no_connect"))
    )
    (net (code "79") (name "unconnected-(U4F-PS_DDR_DQ27_502-PadY4)") (class "Default")
      (node (ref "U4") (pin "Y4") (pinfunction "PS_DDR_DQ27_502_Y4") (pintype "bidirectional+no_connect"))
    )
    (net (code "80") (name "unconnected-(U4F-PS_DDR_DQ28_502-PadY2)") (class "Default")
      (node (ref "U4") (pin "Y2") (pinfunction "PS_DDR_DQ28_502_Y2") (pintype "bidirectional+no_connect"))
    )
    (net (code "81") (name "unconnected-(U4F-PS_DDR_DQ29_502-PadW3)") (class "Default")
      (node (ref "U4") (pin "W3") (pinfunction "PS_DDR_DQ29_502_W3") (pintype "bidirectional+no_connect"))
    )
    (net (code "82") (name "unconnected-(U4F-PS_DDR_DQ30_502-PadV2)") (class "Default")
      (node (ref "U4") (pin "V2") (pinfunction "PS_DDR_DQ30_502_V2") (pintype "bidirectional+no_connect"))
    )
    (net (code "83") (name "unconnected-(U4F-PS_DDR_DQ31_502-PadV3)") (class "Default")
      (node (ref "U4") (pin "V3") (pinfunction "PS_DDR_DQ31_502_V3") (pintype "bidirectional+no_connect"))
    )
    (net (code "84") (name "unconnected-(U4F-PS_DDR_DQS_N2_502-PadT2)") (class "Default")
      (node (ref "U4") (pin "T2") (pinfunction "PS_DDR_DQS_N2_502_T2") (pintype "bidirectional+no_connect"))
    )
    (net (code "85") (name "unconnected-(U4F-PS_DDR_DQS_N3_502-PadW4)") (class "Default")
      (node (ref "U4") (pin "W4") (pinfunction "PS_DDR_DQS_N3_502_W4") (pintype "bidirectional+no_connect"))
    )
    (net (code "86") (name "unconnected-(U4F-PS_DDR_DQS_P2_502-PadR2)") (class "Default")
      (node (ref "U4") (pin "R2") (pinfunction "PS_DDR_DQS_P2_502_R2") (pintype "bidirectional+no_connect"))
    )
    (net (code "87") (name "unconnected-(U4F-PS_DDR_DQS_P3_502-PadW5)") (class "Default")
      (node (ref "U4") (pin "W5") (pinfunction "PS_DDR_DQS_P3_502_W5") (pintype "bidirectional+no_connect"))
    )
    (net (code "88") (name "unconnected-(U15-PGOOD-Pad9)") (class "Default")
      (node (ref "U15") (pin "9") (pinfunction "PGOOD_9") (pintype "open_collector+no_connect"))
    )
  )
)
